# PX4FMUv2_4_6_7.net
KiCad netlist of a schematic drawn in Altium Designer
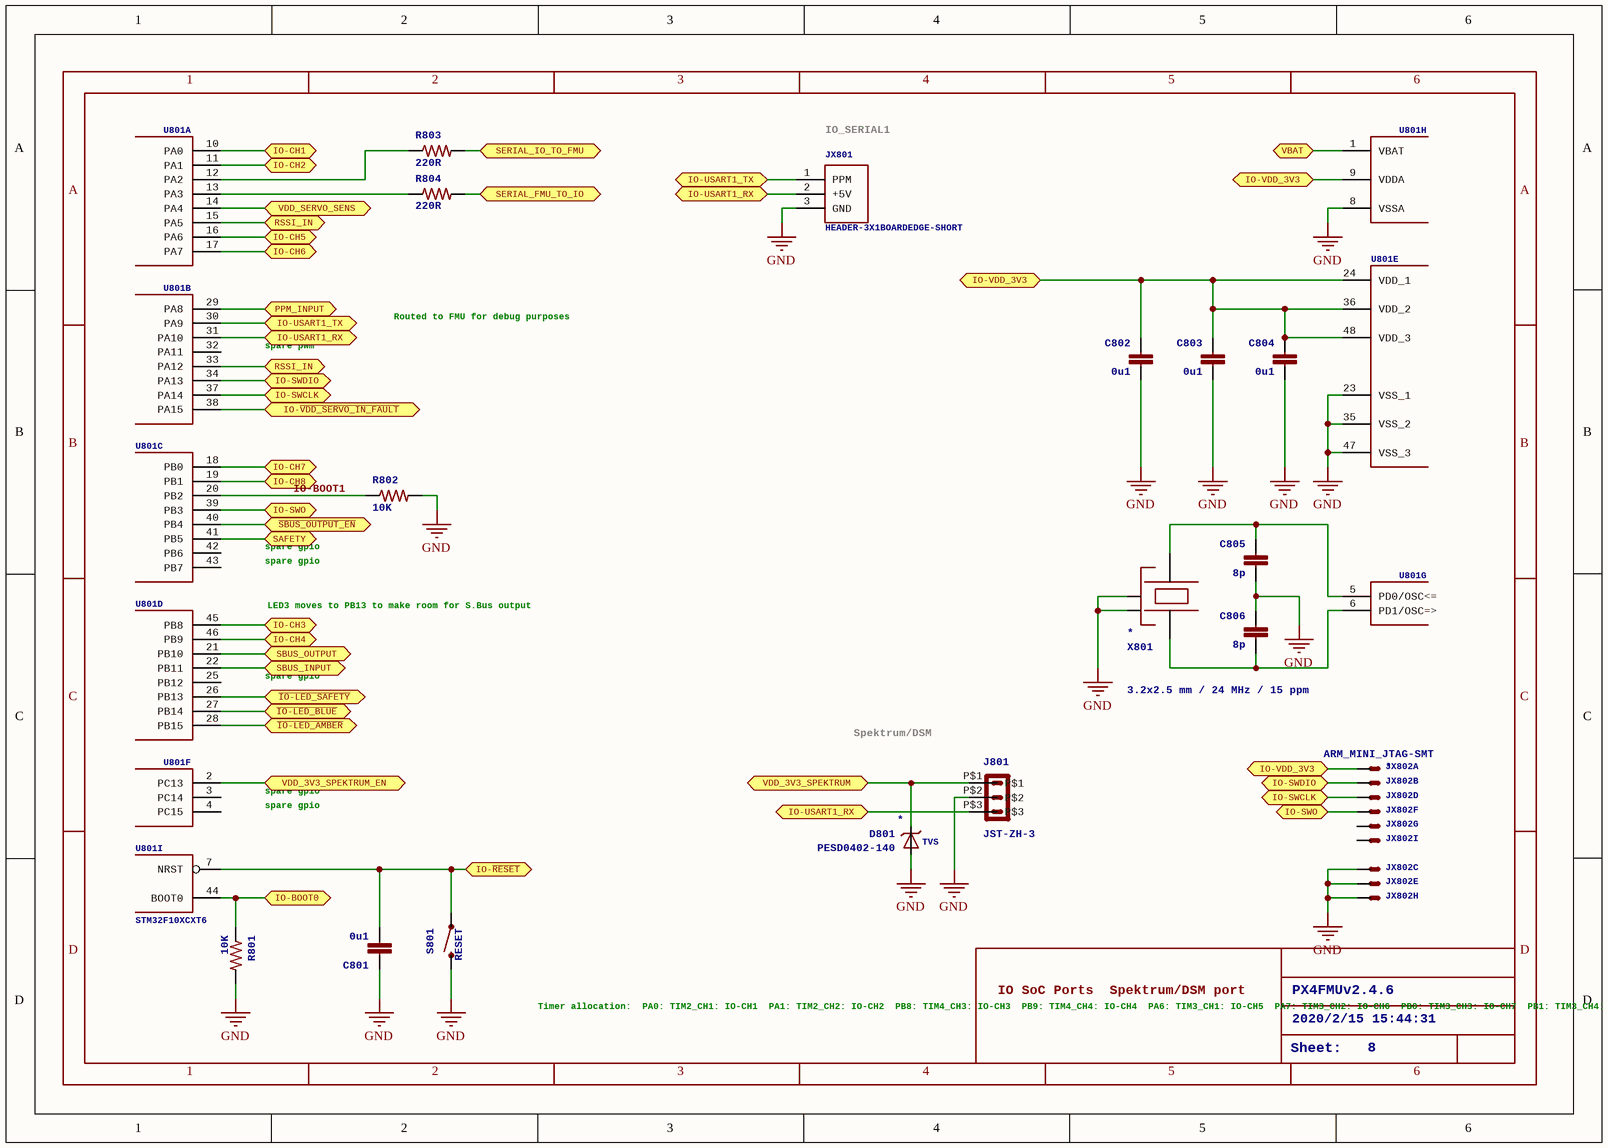
[diagram p0: PX4FMUv2.4.6_7.SchDoc]

(export (version "E")
  (design (tool "Eeschema 10.0.6"))
  (components
    (comp (ref "C801")
      (value "0u1")
      (footprint "0402-CAP")
      (description "CapacitorStandard 0603 ceramic capacitor, and 0.1\" leaded capacitor.")
      (fields (field (name "PARTNO") "CC0402ZRY5V7BB104"))
      (libsource (lib "") (part "CAP0402_1"))
    )
    (comp (ref "C802")
      (value "0u1")
      (footprint "0402-CAP")
      (description "CapacitorStandard 0603 ceramic capacitor, and 0.1\" leaded capacitor.")
      (fields (field (name "PARTNO") "CC0402ZRY5V7BB104"))
      (libsource (lib "pixhawk2") (part "CAP0402"))
    )
    (comp (ref "C803")
      (value "0u1")
      (footprint "0402-CAP")
      (description "CapacitorStandard 0603 ceramic capacitor, and 0.1\" leaded capacitor.")
      (fields (field (name "PARTNO") "CC0402ZRY5V7BB104"))
      (libsource (lib "pixhawk2") (part "CAP0402"))
    )
    (comp (ref "C804")
      (value "0u1")
      (footprint "0402-CAP")
      (description "CapacitorStandard 0603 ceramic capacitor, and 0.1\" leaded capacitor.")
      (fields (field (name "PARTNO") "CC0402ZRY5V7BB104"))
      (libsource (lib "pixhawk2") (part "CAP0402"))
    )
    (comp (ref "C805")
      (value "8p")
      (footprint "0402-CAP")
      (description "CapacitorStandard 0603 ceramic capacitor, and 0.1\" leaded capacitor.")
      (fields (field (name "PARTNO") "C1005C0G1H080C"))
      (libsource (lib "pixhawk2") (part "CAP0402"))
    )
    (comp (ref "C806")
      (value "8p")
      (footprint "0402-CAP")
      (description "CapacitorStandard 0603 ceramic capacitor, and 0.1\" leaded capacitor.")
      (fields (field (name "PARTNO") "C1005C0G1H080C"))
      (libsource (lib "pixhawk2") (part "CAP0402"))
    )
    (comp (ref "D801")
      (value "PESD0402-140")
      (footprint "0402-TVS")
      (fields (field (name "NAME") "*") (field (name "TVS") "TVS"))
      (libsource (lib "pixhawk2") (part "DIODE-TVS"))
    )
    (comp (ref "J801")
      (value "JST-ZH-3")
      (footprint "JST-ZH-SMT-VERTICAL")
      (fields
        (field (name "PARTNO") "B3B-ZR-SM4-TF (LF)(SN)(P)")
        (field (name "LIBRARYNAME") "for-transfers")
      )
      (libsource (lib "for-transfers") (part "JST-ZH-3"))
    )
    (comp (ref "JX801")
      (value "HEADER-3X1BOARDEDGE-SHORT")
      (footprint "HEADER_3X01_SMD_H_BOARD_EDGE_SHORT")
      (description "Single row 0.1\" servo header")
      (libsource (lib "pixhawk2") (part "HEADER-3X1BOARDEDGE-SHORT"))
    )
    (comp (ref "JX802")
      (value "ARM_MINI_JTAG-SMT")
      (footprint "FTSH-105-01-XXX-DV-K")
      (description "CONNECTORwire to board 1.25 mm (.049 inch) pitch header")
      (fields (field (name "PARTNO") "M50-3900542") (field (name "NAME") "*"))
      (libsource (lib "pixhawk2") (part "ARM_MINI_JTAG-SMT"))
    )
    (comp (ref "R801")
      (value "10K")
      (footprint "0402-RES")
      (fields (field (name "PARTNO") "RC0402FR-0710KL"))
      (libsource (lib "pixhawk2") (part "RESISTOR0402-RES"))
    )
    (comp (ref "R802")
      (value "10K")
      (footprint "0402-RES")
      (fields (field (name "PARTNO") "RC0402FR-0710KL"))
      (libsource (lib "pixhawk2") (part "RESISTOR0402-RES"))
    )
    (comp (ref "R803")
      (value "220R")
      (footprint "0402-RES")
      (fields (field (name "PARTNO") "RC0402FR-07220RL"))
      (libsource (lib "pixhawk2") (part "RESISTOR0402-RES"))
    )
    (comp (ref "R804")
      (value "220R")
      (footprint "0402-RES")
      (fields (field (name "PARTNO") "RC0402FR-07220RL"))
      (libsource (lib "pixhawk2") (part "RESISTOR0402-RES"))
    )
    (comp (ref "S801")
      (value "RESET")
      (footprint "EVQP7J01K")
      (fields (field (name "PARTNO") "EVQ-P7J01P"))
      (libsource (lib "pixhawk2") (part "SWITCH-MOMENTARY-2"))
    )
    (comp (ref "U801")
      (value "STM32F10XCXT6")
      (footprint "TQFP48")
      (description "ST STM32F101/103 48pin LQFP")
      (fields (field (name "PARTNO") "STM32F100C8T6B"))
      (libsource (lib "pixhawk2") (part "STM32F10XCXT6"))
    )
    (comp (ref "X801")
      (value "3.2x2.5 mm / 24 MHz / 15 ppm")
      (footprint "OSCILLATOR-3.2X2.5")
      (description "Crystal Oscillator in 3.2x2.5 SMD")
      (fields (field (name "NAME") "*") (field (name "PARTNO") "NX3225SA-24.000000MHZ"))
      (libsource (lib "pixhawk2") (part "OSCILLATOR-3.2X2.5"))
    )
  )
  (nets
    (net (code "1") (name "/IO-BOOT0") (class "Default")
      (node (ref "R801") (pin "P$1") (pinfunction "1_P$1") (pintype "passive"))
      (node (ref "U801") (pin "44") (pinfunction "BOOT0_44") (pintype "passive"))
    )
    (net (code "2") (name "/IO-BOOT1") (class "Default")
      (node (ref "R802") (pin "P$1") (pinfunction "1_P$1") (pintype "passive"))
      (node (ref "U801") (pin "20") (pinfunction "PB2_20") (pintype "passive"))
    )
    (net (code "3") (name "/IO-CH1") (class "Default")
      (node (ref "U801") (pin "10") (pinfunction "PA0_10") (pintype "passive"))
    )
    (net (code "4") (name "/IO-CH2") (class "Default")
      (node (ref "U801") (pin "11") (pinfunction "PA1_11") (pintype "passive"))
    )
    (net (code "5") (name "/IO-CH3") (class "Default")
      (node (ref "U801") (pin "45") (pinfunction "PB8_45") (pintype "passive"))
    )
    (net (code "6") (name "/IO-CH4") (class "Default")
      (node (ref "U801") (pin "46") (pinfunction "PB9_46") (pintype "passive"))
    )
    (net (code "7") (name "/IO-CH5") (class "Default")
      (node (ref "U801") (pin "16") (pinfunction "PA6_16") (pintype "passive"))
    )
    (net (code "8") (name "/IO-CH6") (class "Default")
      (node (ref "U801") (pin "17") (pinfunction "PA7_17") (pintype "passive"))
    )
    (net (code "9") (name "/IO-CH7") (class "Default")
      (node (ref "U801") (pin "18") (pinfunction "PB0_18") (pintype "passive"))
    )
    (net (code "10") (name "/IO-CH8") (class "Default")
      (node (ref "U801") (pin "19") (pinfunction "PB1_19") (pintype "passive"))
    )
    (net (code "11") (name "/IO-SWCLK") (class "Default")
      (node (ref "JX802") (pin "4") (pinfunction "S_4") (pintype "passive"))
      (node (ref "U801") (pin "37") (pinfunction "PA14_37") (pintype "passive"))
    )
    (net (code "12") (name "/IO-SWDIO") (class "Default")
      (node (ref "JX802") (pin "2") (pinfunction "S_2") (pintype "passive"))
      (node (ref "U801") (pin "34") (pinfunction "PA13_34") (pintype "passive"))
    )
    (net (code "13") (name "/IO-SWO") (class "Default")
      (node (ref "JX802") (pin "6") (pinfunction "S_6") (pintype "passive"))
      (node (ref "U801") (pin "39") (pinfunction "PB3_39") (pintype "passive"))
    )
    (net (code "14") (name "/IO-USART1_RX") (class "Default")
      (node (ref "J801") (pin "P$3") (pinfunction "P$3_P$3") (pintype "passive"))
      (node (ref "JX801") (pin "2") (pinfunction "+5V_2") (pintype "passive"))
      (node (ref "U801") (pin "31") (pinfunction "PA10_31") (pintype "passive"))
    )
    (net (code "15") (name "/IO-USART1_TX") (class "Default")
      (node (ref "JX801") (pin "1") (pinfunction "PPM_1") (pintype "passive"))
      (node (ref "U801") (pin "30") (pinfunction "PA9_30") (pintype "passive"))
    )
    (net (code "16") (name "/IO-VDD_3V3") (class "Default")
      (node (ref "C802") (pin "P$1") (pinfunction "1_P$1") (pintype "passive"))
      (node (ref "C803") (pin "P$1") (pinfunction "1_P$1") (pintype "passive"))
      (node (ref "C804") (pin "P$1") (pinfunction "1_P$1") (pintype "passive"))
      (node (ref "JX802") (pin "1") (pinfunction "S_1") (pintype "passive"))
      (node (ref "U801") (pin "24") (pinfunction "VDD_1_24") (pintype "power_in"))
      (node (ref "U801") (pin "36") (pinfunction "VDD_2_36") (pintype "power_in"))
      (node (ref "U801") (pin "48") (pinfunction "VDD_3_48") (pintype "power_in"))
      (node (ref "U801") (pin "9") (pinfunction "VDDA_9") (pintype "power_in"))
    )
    (net (code "17") (name "/IO-~{RESET}") (class "Default")
      (node (ref "C801") (pin "P$2") (pinfunction "2_P$2") (pintype "passive"))
      (node (ref "S801") (pin "A1") (pinfunction "1_A1") (pintype "passive"))
      (node (ref "U801") (pin "7") (pinfunction "NRST_7") (pintype "passive"))
    )
    (net (code "18") (name "/IO-~{VDD_SERVO_IN_FAULT}") (class "Default")
      (node (ref "U801") (pin "38") (pinfunction "PA15_38") (pintype "passive"))
    )
    (net (code "19") (name "/PPM_INPUT") (class "Default")
      (node (ref "U801") (pin "29") (pinfunction "PA8_29") (pintype "passive"))
    )
    (net (code "20") (name "/RSSI_IN") (class "Default")
      (node (ref "U801") (pin "15") (pinfunction "PA5_15") (pintype "passive"))
      (node (ref "U801") (pin "33") (pinfunction "PA12_33") (pintype "passive"))
    )
    (net (code "21") (name "/SAFETY") (class "Default")
      (node (ref "U801") (pin "41") (pinfunction "PB5_41") (pintype "passive"))
    )
    (net (code "22") (name "/SBUS_INPUT") (class "Default")
      (node (ref "U801") (pin "22") (pinfunction "PB11_22") (pintype "passive"))
    )
    (net (code "23") (name "/SBUS_OUTPUT") (class "Default")
      (node (ref "U801") (pin "21") (pinfunction "PB10_21") (pintype "passive"))
    )
    (net (code "24") (name "/SERIAL_FMU_TO_IO") (class "Default")
      (node (ref "R804") (pin "P$2") (pinfunction "2_P$2") (pintype "passive"))
    )
    (net (code "25") (name "/SERIAL_IO_TO_FMU") (class "Default")
      (node (ref "R803") (pin "P$2") (pinfunction "2_P$2") (pintype "passive"))
    )
    (net (code "26") (name "/VBAT") (class "Default")
      (node (ref "U801") (pin "1") (pinfunction "VBAT_1") (pintype "power_in"))
    )
    (net (code "27") (name "/VDD_3V3_SPEKTRUM") (class "Default")
      (node (ref "D801") (pin "C") (pinfunction "C_C") (pintype "passive"))
      (node (ref "J801") (pin "P$1") (pinfunction "P$1_P$1") (pintype "passive"))
    )
    (net (code "28") (name "/VDD_3V3_SPEKTRUM_EN") (class "Default")
      (node (ref "U801") (pin "2") (pinfunction "PC13_2") (pintype "passive"))
    )
    (net (code "29") (name "/VDD_SERVO_SENS") (class "Default")
      (node (ref "U801") (pin "14") (pinfunction "PA4_14") (pintype "passive"))
    )
    (net (code "30") (name "/~{IO-LED_AMBER}") (class "Default")
      (node (ref "U801") (pin "28") (pinfunction "PB15_28") (pintype "passive"))
    )
    (net (code "31") (name "/~{IO-LED_BLUE}") (class "Default")
      (node (ref "U801") (pin "27") (pinfunction "PB14_27") (pintype "passive"))
    )
    (net (code "32") (name "/~{IO-LED_SAFETY}") (class "Default")
      (node (ref "U801") (pin "26") (pinfunction "PB13_26") (pintype "passive"))
    )
    (net (code "33") (name "/~{SBUS_OUTPUT_EN}") (class "Default")
      (node (ref "U801") (pin "40") (pinfunction "PB4_40") (pintype "passive"))
    )
    (net (code "34") (name "GND") (class "Default")
      (node (ref "C801") (pin "P$1") (pinfunction "1_P$1") (pintype "passive"))
      (node (ref "C802") (pin "P$2") (pinfunction "2_P$2") (pintype "passive"))
      (node (ref "C803") (pin "P$2") (pinfunction "2_P$2") (pintype "passive"))
      (node (ref "C804") (pin "P$2") (pinfunction "2_P$2") (pintype "passive"))
      (node (ref "C805") (pin "P$2") (pinfunction "2_P$2") (pintype "passive"))
      (node (ref "C806") (pin "P$1") (pinfunction "1_P$1") (pintype "passive"))
      (node (ref "D801") (pin "A") (pinfunction "A_A") (pintype "passive"))
      (node (ref "J801") (pin "P$2") (pinfunction "P$2_P$2") (pintype "passive"))
      (node (ref "JX801") (pin "3") (pinfunction "GND_3") (pintype "passive"))
      (node (ref "JX802") (pin "3") (pinfunction "S_3") (pintype "passive"))
      (node (ref "JX802") (pin "5") (pinfunction "S_5") (pintype "passive"))
      (node (ref "JX802") (pin "9") (pinfunction "S_9") (pintype "passive"))
      (node (ref "R801") (pin "P$2") (pinfunction "2_P$2") (pintype "passive"))
      (node (ref "R802") (pin "P$2") (pinfunction "2_P$2") (pintype "passive"))
      (node (ref "S801") (pin "B3") (pinfunction "2_B3") (pintype "passive"))
      (node (ref "U801") (pin "23") (pinfunction "VSS_1_23") (pintype "power_in"))
      (node (ref "U801") (pin "35") (pinfunction "VSS_2_35") (pintype "power_in"))
      (node (ref "U801") (pin "47") (pinfunction "VSS_3_47") (pintype "power_in"))
      (node (ref "U801") (pin "8") (pinfunction "VSSA_8") (pintype "power_in"))
      (node (ref "X801") (pin "2") (pinfunction "NC_2_2") (pintype "open_emitter"))
      (node (ref "X801") (pin "4") (pinfunction "NC_4_4") (pintype "open_emitter"))
    )
    (net (code "35") (name "Net-(C805-1)") (class "Default")
      (node (ref "C805") (pin "P$1") (pinfunction "1_P$1") (pintype "passive"))
      (node (ref "U801") (pin "5") (pinfunction "PD0/OSC<=_5") (pintype "passive"))
      (node (ref "X801") (pin "3") (pinfunction "3_3") (pintype "passive"))
    )
    (net (code "36") (name "Net-(C806-2)") (class "Default")
      (node (ref "C806") (pin "P$2") (pinfunction "2_P$2") (pintype "passive"))
      (node (ref "U801") (pin "6") (pinfunction "PD1/OSC=>_6") (pintype "passive"))
      (node (ref "X801") (pin "1") (pinfunction "1_1") (pintype "passive"))
    )
    (net (code "37") (name "Net-(R803-1)") (class "Default")
      (node (ref "R803") (pin "P$1") (pinfunction "1_P$1") (pintype "passive"))
      (node (ref "U801") (pin "12") (pinfunction "PA2_12") (pintype "passive"))
    )
    (net (code "38") (name "Net-(R804-1)") (class "Default")
      (node (ref "R804") (pin "P$1") (pinfunction "1_P$1") (pintype "passive"))
      (node (ref "U801") (pin "13") (pinfunction "PA3_13") (pintype "passive"))
    )
    (net (code "39") (name "unconnected-(JX802G-S-Pad8)") (class "Default")
      (node (ref "JX802") (pin "8") (pinfunction "S_8") (pintype "passive"))
    )
    (net (code "40") (name "unconnected-(JX802I-S-Pad10)") (class "Default")
      (node (ref "JX802") (pin "10") (pinfunction "S_10") (pintype "passive"))
    )
    (net (code "41") (name "unconnected-(U801B-PA11-Pad32)") (class "Default")
      (node (ref "U801") (pin "32") (pinfunction "PA11_32") (pintype "passive"))
    )
    (net (code "42") (name "unconnected-(U801C-PB6-Pad42)") (class "Default")
      (node (ref "U801") (pin "42") (pinfunction "PB6_42") (pintype "passive"))
    )
    (net (code "43") (name "unconnected-(U801C-PB7-Pad43)") (class "Default")
      (node (ref "U801") (pin "43") (pinfunction "PB7_43") (pintype "passive"))
    )
    (net (code "44") (name "unconnected-(U801D-PB12-Pad25)") (class "Default")
      (node (ref "U801") (pin "25") (pinfunction "PB12_25") (pintype "passive"))
    )
    (net (code "45") (name "unconnected-(U801F-PC14-Pad3)") (class "Default")
      (node (ref "U801") (pin "3") (pinfunction "PC14_3") (pintype "passive"))
    )
    (net (code "46") (name "unconnected-(U801F-PC15-Pad4)") (class "Default")
      (node (ref "U801") (pin "4") (pinfunction "PC15_4") (pintype "passive"))
    )
  )
)
